# mcu_teensy4_1.net
KiCad netlist of a schematic drawn in EAGLE
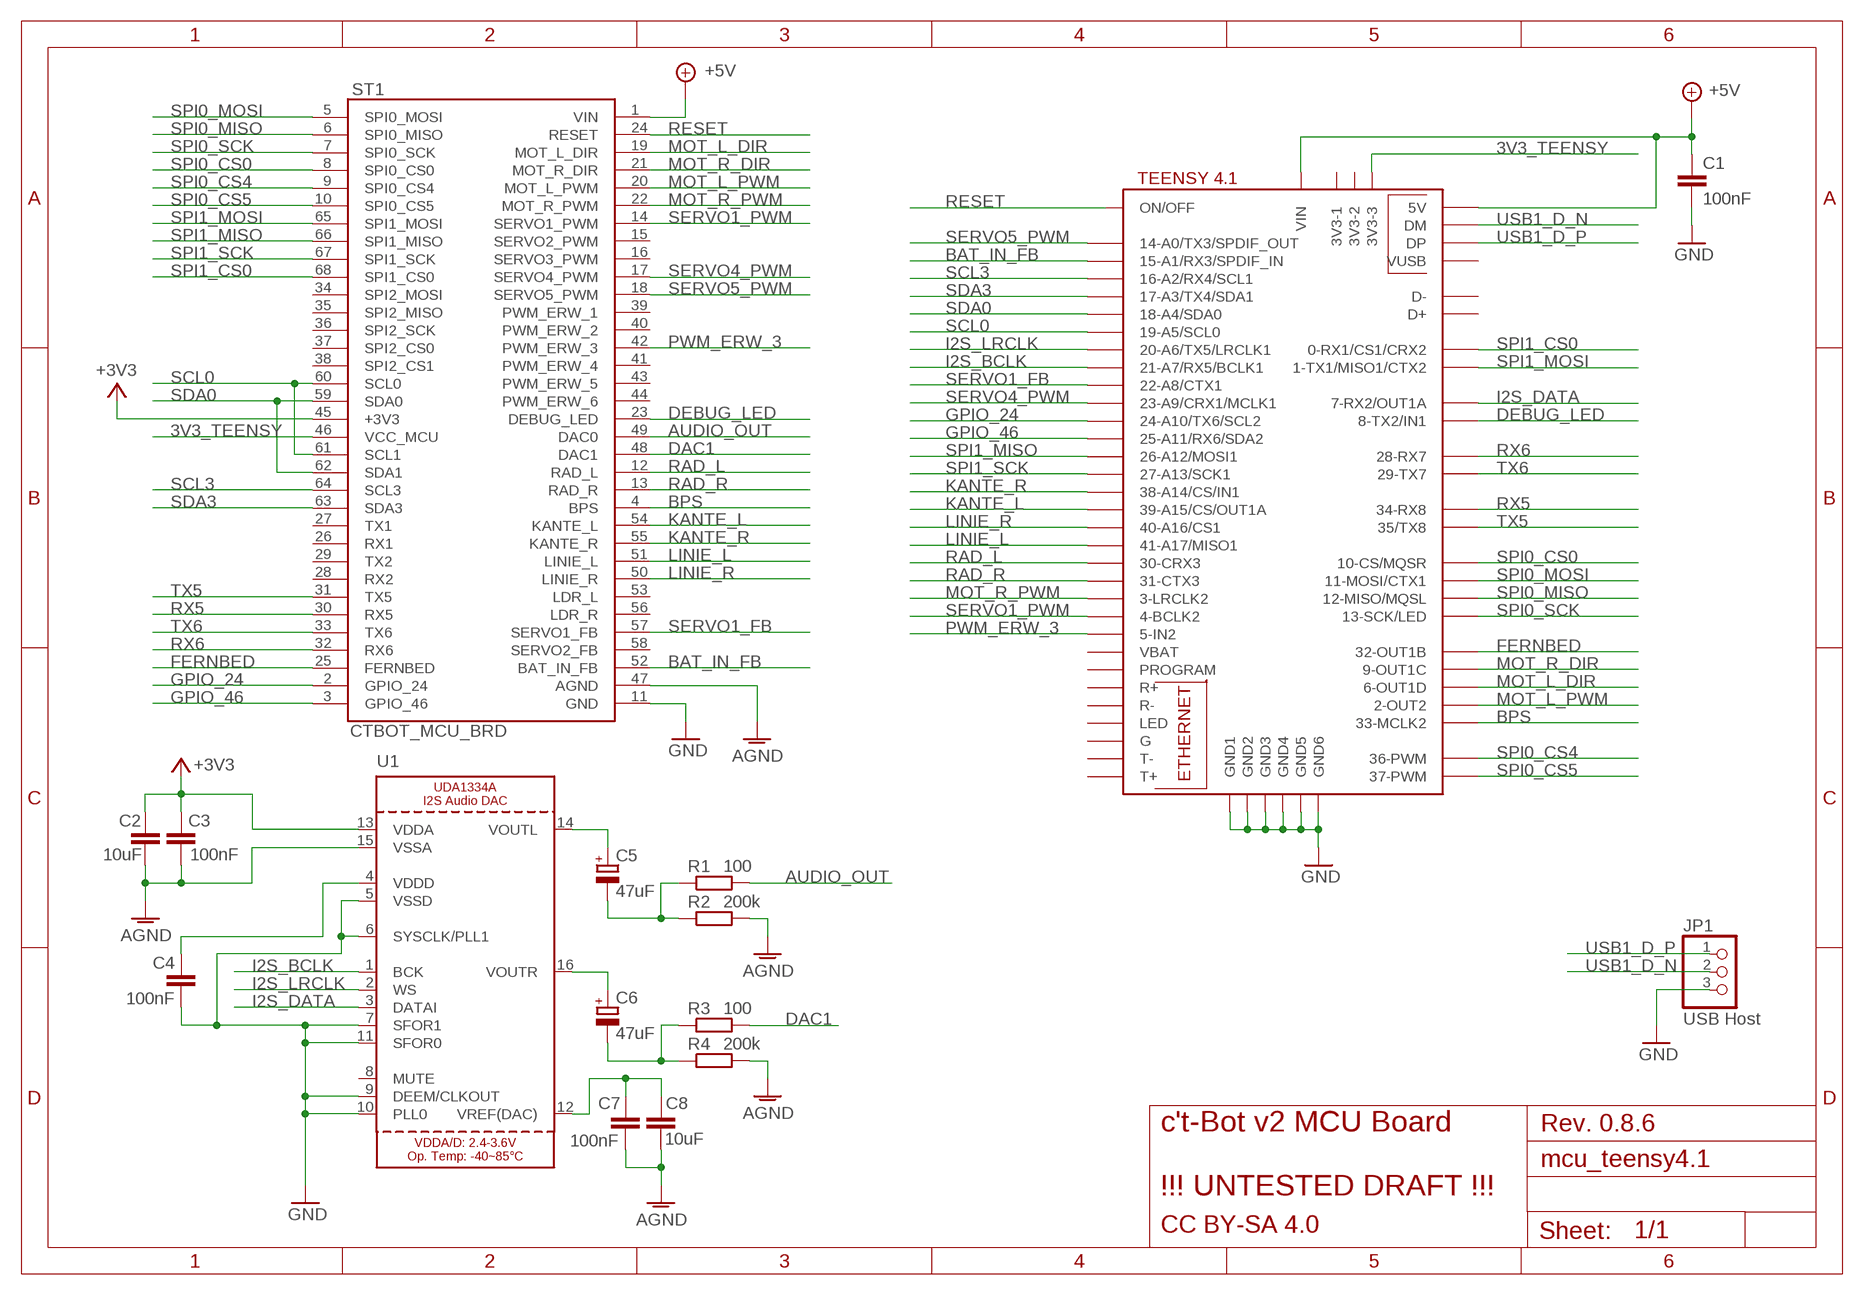
[diagram p0: schematic, sheet 1]

(export (version "E")
  (design (tool "Eeschema 10.0.6"))
  (components
    (comp (ref "C1")
      (value "100nF")
      (footprint "eagle-import:C0805")
      (libsource (lib "eagle-import") (part "C-EUC0805"))
    )
    (comp (ref "C2")
      (value "10uF")
      (footprint "eagle-import:C0805")
      (libsource (lib "eagle-import") (part "C-EUC0805"))
    )
    (comp (ref "C3")
      (value "100nF")
      (footprint "eagle-import:C0805")
      (libsource (lib "eagle-import") (part "C-EUC0805"))
    )
    (comp (ref "C4")
      (value "100nF")
      (footprint "eagle-import:C0805")
      (libsource (lib "eagle-import") (part "C-EUC0805"))
    )
    (comp (ref "C5")
      (value "47uF")
      (footprint "eagle-import:UD-6,3X5,8_NICHICON")
      (libsource (lib "eagle-import") (part "CPOL-EUUD-6,3X8,8"))
    )
    (comp (ref "C6")
      (value "47uF")
      (footprint "eagle-import:UD-6,3X5,8_NICHICON")
      (libsource (lib "eagle-import") (part "CPOL-EUUD-6,3X8,8"))
    )
    (comp (ref "C7")
      (value "100nF")
      (footprint "eagle-import:C0805")
      (libsource (lib "eagle-import") (part "C-EUC0805"))
    )
    (comp (ref "C8")
      (value "10uF")
      (footprint "eagle-import:C0805")
      (libsource (lib "eagle-import") (part "C-EUC0805"))
    )
    (comp (ref "JP1")
      (value "USB Host")
      (footprint "eagle-import:1X03_90")
      (libsource (lib "eagle-import") (part "PINHD-1X3/90"))
    )
    (comp (ref "R1")
      (value "100")
      (footprint "eagle-import:R0805")
      (libsource (lib "eagle-import") (part "R-EU_R0805"))
    )
    (comp (ref "R2")
      (value "200k")
      (footprint "eagle-import:R0805")
      (libsource (lib "eagle-import") (part "R-EU_R0805"))
    )
    (comp (ref "R3")
      (value "100")
      (footprint "eagle-import:R0805")
      (libsource (lib "eagle-import") (part "R-EU_R0805"))
    )
    (comp (ref "R4")
      (value "200k")
      (footprint "eagle-import:R0805")
      (libsource (lib "eagle-import") (part "R-EU_R0805"))
    )
    (comp (ref "ST1")
      (value "CTBOT_MCU_BRD")
      (footprint "eagle-import:DIP66")
      (libsource (lib "eagle-import") (part "CTBOT_MCU_BRD"))
    )
    (comp (ref "U$1")
      (value "TEENSY41")
      (footprint "eagle-import:TEENSY41")
      (libsource (lib "eagle-import") (part "TEENSY41"))
    )
    (comp (ref "U1")
      (value "AUDIO_I2S_UDA1334\"\"")
      (footprint "eagle-import:SSOP16_4.4MM")
      (libsource (lib "eagle-import") (part "AUDIO_I2S_UDA1334{dblquote}{dblquote}"))
    )
  )
  (nets
    (net (code "1") (name "+3V3") (class "Default")
      (node (ref "C2") (pin "1") (pinfunction "1_1") (pintype "passive"))
      (node (ref "C3") (pin "2") (pinfunction "2_2") (pintype "passive"))
      (node (ref "ST1") (pin "45") (pinfunction "+3V3_45") (pintype "power_in"))
      (node (ref "U1") (pin "13") (pinfunction "VDDA_13") (pintype "power_in"))
    )
    (net (code "2") (name "+5V") (class "Default")
      (node (ref "C1") (pin "1") (pinfunction "1_1") (pintype "passive"))
      (node (ref "ST1") (pin "1") (pinfunction "VIN_1") (pintype "power_in"))
      (node (ref "U$1") (pin "+5V") (pinfunction "5V_+5V") (pintype "bidirectional"))
      (node (ref "U$1") (pin "VIN") (pinfunction "VIN_VIN") (pintype "bidirectional"))
    )
    (net (code "3") (name "/3V3_TEENSY") (class "Default")
      (node (ref "ST1") (pin "46") (pinfunction "VCC_MCU_46") (pintype "power_in"))
      (node (ref "U$1") (pin "3V3-3") (pinfunction "3V3-3_3V3-3") (pintype "bidirectional"))
    )
    (net (code "4") (name "/AUDIO_OUT") (class "Default")
      (node (ref "R1") (pin "2") (pinfunction "2_2") (pintype "passive"))
      (node (ref "ST1") (pin "49") (pinfunction "DAC0_49") (pintype "bidirectional"))
    )
    (net (code "5") (name "/BAT_IN_FB") (class "Default")
      (node (ref "ST1") (pin "52") (pinfunction "BAT_IN_FB_52") (pintype "input"))
      (node (ref "U$1") (pin "15-A1/RX3/SPDIF_IN") (pinfunction "15-A1/RX3/SPDIF_IN_15-A1/RX3/SPDIF_IN") (pintype "bidirectional"))
    )
    (net (code "6") (name "/BPS") (class "Default")
      (node (ref "ST1") (pin "4") (pinfunction "BPS_4") (pintype "input"))
      (node (ref "U$1") (pin "33-MCLK2") (pinfunction "33-MCLK2_33-MCLK2") (pintype "bidirectional"))
    )
    (net (code "7") (name "/DAC1") (class "Default")
      (node (ref "R3") (pin "2") (pinfunction "2_2") (pintype "passive"))
      (node (ref "ST1") (pin "48") (pinfunction "DAC1_48") (pintype "bidirectional"))
    )
    (net (code "8") (name "/DEBUG_LED") (class "Default")
      (node (ref "ST1") (pin "23") (pinfunction "DEBUG_LED_23") (pintype "output"))
      (node (ref "U$1") (pin "8-TX2/IN1") (pinfunction "8-TX2/IN1_8-TX2/IN1") (pintype "bidirectional"))
    )
    (net (code "9") (name "/FERNBED") (class "Default")
      (node (ref "ST1") (pin "25") (pinfunction "FERNBED_25") (pintype "bidirectional"))
      (node (ref "U$1") (pin "32-OUT1B") (pinfunction "32-OUT1B_32-OUT1B") (pintype "bidirectional"))
    )
    (net (code "10") (name "/GPIO_24") (class "Default")
      (node (ref "ST1") (pin "2") (pinfunction "GPIO_24_2") (pintype "bidirectional"))
      (node (ref "U$1") (pin "24-A10/TX6/SCL2") (pinfunction "24-A10/TX6/SCL2_24-A10/TX6/SCL2") (pintype "bidirectional"))
    )
    (net (code "11") (name "/GPIO_46") (class "Default")
      (node (ref "ST1") (pin "3") (pinfunction "GPIO_46_3") (pintype "bidirectional"))
      (node (ref "U$1") (pin "25-A11/RX6/SDA2") (pinfunction "25-A11/RX6/SDA2_25-A11/RX6/SDA2") (pintype "bidirectional"))
    )
    (net (code "12") (name "/I2S_BCLK") (class "Default")
      (node (ref "U$1") (pin "21-A7/RX5/BCLK1") (pinfunction "21-A7/RX5/BCLK1_21-A7/RX5/BCLK1") (pintype "bidirectional"))
      (node (ref "U1") (pin "1") (pinfunction "BCK_1") (pintype "input"))
    )
    (net (code "13") (name "/I2S_DATA") (class "Default")
      (node (ref "U$1") (pin "7-RX2/OUT1A") (pinfunction "7-RX2/OUT1A_7-RX2/OUT1A") (pintype "bidirectional"))
      (node (ref "U1") (pin "3") (pinfunction "DATAI_3") (pintype "input"))
    )
    (net (code "14") (name "/I2S_LRCLK") (class "Default")
      (node (ref "U$1") (pin "20-A6/TX5/LRCLK1") (pinfunction "20-A6/TX5/LRCLK1_20-A6/TX5/LRCLK1") (pintype "bidirectional"))
      (node (ref "U1") (pin "2") (pinfunction "WS_2") (pintype "input"))
    )
    (net (code "15") (name "/KANTE_L") (class "Default")
      (node (ref "ST1") (pin "54") (pinfunction "KANTE_L_54") (pintype "input"))
      (node (ref "U$1") (pin "39-A15/CS/OUT1A") (pinfunction "39-A15/CS/OUT1A_39-A15/CS/OUT1A") (pintype "bidirectional"))
    )
    (net (code "16") (name "/KANTE_R") (class "Default")
      (node (ref "ST1") (pin "55") (pinfunction "KANTE_R_55") (pintype "input"))
      (node (ref "U$1") (pin "38-A14/CS/IN1") (pinfunction "38-A14/CS/IN1_38-A14/CS/IN1") (pintype "bidirectional"))
    )
    (net (code "17") (name "/LINIE_L") (class "Default")
      (node (ref "ST1") (pin "51") (pinfunction "LINIE_L_51") (pintype "input"))
      (node (ref "U$1") (pin "41-A17/MISO1") (pinfunction "41-A17/MISO1_41-A17/MISO1") (pintype "bidirectional"))
    )
    (net (code "18") (name "/LINIE_R") (class "Default")
      (node (ref "ST1") (pin "50") (pinfunction "LINIE_R_50") (pintype "input"))
      (node (ref "U$1") (pin "40-A16/CS1") (pinfunction "40-A16/CS1_40-A16/CS1") (pintype "bidirectional"))
    )
    (net (code "19") (name "/MOT_L_DIR") (class "Default")
      (node (ref "ST1") (pin "19") (pinfunction "MOT_L_DIR_19") (pintype "output"))
      (node (ref "U$1") (pin "6-OUT1D") (pinfunction "6-OUT1D_6-OUT1D") (pintype "bidirectional"))
    )
    (net (code "20") (name "/MOT_L_PWM") (class "Default")
      (node (ref "ST1") (pin "20") (pinfunction "MOT_L_PWM_20") (pintype "output"))
      (node (ref "U$1") (pin "2-OUT2") (pinfunction "2-OUT2_2-OUT2") (pintype "bidirectional"))
    )
    (net (code "21") (name "/MOT_R_DIR") (class "Default")
      (node (ref "ST1") (pin "21") (pinfunction "MOT_R_DIR_21") (pintype "output"))
      (node (ref "U$1") (pin "9-OUT1C") (pinfunction "9-OUT1C_9-OUT1C") (pintype "bidirectional"))
    )
    (net (code "22") (name "/MOT_R_PWM") (class "Default")
      (node (ref "ST1") (pin "22") (pinfunction "MOT_R_PWM_22") (pintype "output"))
      (node (ref "U$1") (pin "3-LRCLK2") (pinfunction "3-LRCLK2_3-LRCLK2") (pintype "bidirectional"))
    )
    (net (code "23") (name "/PWM_ERW_3") (class "Default")
      (node (ref "ST1") (pin "42") (pinfunction "PWM_ERW_3_42") (pintype "bidirectional"))
      (node (ref "U$1") (pin "5-IN2") (pinfunction "5-IN2_5-IN2") (pintype "bidirectional"))
    )
    (net (code "24") (name "/RAD_L") (class "Default")
      (node (ref "ST1") (pin "12") (pinfunction "RAD_L_12") (pintype "input"))
      (node (ref "U$1") (pin "30-CRX3") (pinfunction "30-CRX3_30-CRX3") (pintype "bidirectional"))
    )
    (net (code "25") (name "/RAD_R") (class "Default")
      (node (ref "ST1") (pin "13") (pinfunction "RAD_R_13") (pintype "input"))
      (node (ref "U$1") (pin "31-CTX3") (pinfunction "31-CTX3_31-CTX3") (pintype "bidirectional"))
    )
    (net (code "26") (name "/RESET") (class "Default")
      (node (ref "ST1") (pin "24") (pinfunction "RESET_24") (pintype "input"))
      (node (ref "U$1") (pin "ON/OFF") (pinfunction "ON/OFF_ON/OFF") (pintype "bidirectional"))
    )
    (net (code "27") (name "/RX5") (class "Default")
      (node (ref "ST1") (pin "30") (pinfunction "RX5_30") (pintype "input"))
      (node (ref "U$1") (pin "34-RX8") (pinfunction "34-RX8_34-RX8") (pintype "bidirectional"))
    )
    (net (code "28") (name "/RX6") (class "Default")
      (node (ref "ST1") (pin "32") (pinfunction "RX6_32") (pintype "input"))
      (node (ref "U$1") (pin "28-RX7") (pinfunction "28-RX7_28-RX7") (pintype "bidirectional"))
    )
    (net (code "29") (name "/SCL0") (class "Default")
      (node (ref "ST1") (pin "60") (pinfunction "SCL0_60") (pintype "output"))
      (node (ref "ST1") (pin "61") (pinfunction "SCL1_61") (pintype "output"))
      (node (ref "U$1") (pin "19-A5/SCL0") (pinfunction "19-A5/SCL0_19-A5/SCL0") (pintype "bidirectional"))
    )
    (net (code "30") (name "/SCL3") (class "Default")
      (node (ref "ST1") (pin "64") (pinfunction "SCL3_64") (pintype "output"))
      (node (ref "U$1") (pin "16-A2/RX4/SCL1") (pinfunction "16-A2/RX4/SCL1_16-A2/RX4/SCL1") (pintype "bidirectional"))
    )
    (net (code "31") (name "/SDA0") (class "Default")
      (node (ref "ST1") (pin "59") (pinfunction "SDA0_59") (pintype "bidirectional"))
      (node (ref "ST1") (pin "62") (pinfunction "SDA1_62") (pintype "bidirectional"))
      (node (ref "U$1") (pin "18-A4/SDA0") (pinfunction "18-A4/SDA0_18-A4/SDA0") (pintype "bidirectional"))
    )
    (net (code "32") (name "/SDA3") (class "Default")
      (node (ref "ST1") (pin "63") (pinfunction "SDA3_63") (pintype "bidirectional"))
      (node (ref "U$1") (pin "17-A3/TX4/SDA1") (pinfunction "17-A3/TX4/SDA1_17-A3/TX4/SDA1") (pintype "bidirectional"))
    )
    (net (code "33") (name "/SERVO1_FB") (class "Default")
      (node (ref "ST1") (pin "57") (pinfunction "SERVO1_FB_57") (pintype "input"))
      (node (ref "U$1") (pin "22-A8/CTX1") (pinfunction "22-A8/CTX1_22-A8/CTX1") (pintype "bidirectional"))
    )
    (net (code "34") (name "/SERVO1_PWM") (class "Default")
      (node (ref "ST1") (pin "14") (pinfunction "SERVO1_PWM_14") (pintype "output"))
      (node (ref "U$1") (pin "4-BCLK2") (pinfunction "4-BCLK2_4-BCLK2") (pintype "bidirectional"))
    )
    (net (code "35") (name "/SERVO4_PWM") (class "Default")
      (node (ref "ST1") (pin "17") (pinfunction "SERVO4_PWM_17") (pintype "bidirectional"))
      (node (ref "U$1") (pin "23-A9/CRX1/MCLK1") (pinfunction "23-A9/CRX1/MCLK1_23-A9/CRX1/MCLK1") (pintype "bidirectional"))
    )
    (net (code "36") (name "/SERVO5_PWM") (class "Default")
      (node (ref "ST1") (pin "18") (pinfunction "SERVO5_PWM_18") (pintype "bidirectional"))
      (node (ref "U$1") (pin "14-A0/TX3/SPDIF_OUT") (pinfunction "14-A0/TX3/SPDIF_OUT_14-A0/TX3/SPDIF_OUT") (pintype "bidirectional"))
    )
    (net (code "37") (name "/SPI0_CS0") (class "Default")
      (node (ref "ST1") (pin "8") (pinfunction "SPI0_CS0_8") (pintype "bidirectional"))
      (node (ref "U$1") (pin "10-CS\\MQSR") (pinfunction "10-CS/MQSR_10-CS\\MQSR") (pintype "bidirectional"))
    )
    (net (code "38") (name "/SPI0_CS4") (class "Default")
      (node (ref "ST1") (pin "9") (pinfunction "SPI0_CS4_9") (pintype "bidirectional"))
      (node (ref "U$1") (pin "36-PWM") (pinfunction "36-PWM_36-PWM") (pintype "bidirectional"))
    )
    (net (code "39") (name "/SPI0_CS5") (class "Default")
      (node (ref "ST1") (pin "10") (pinfunction "SPI0_CS5_10") (pintype "bidirectional"))
      (node (ref "U$1") (pin "37-PWM") (pinfunction "37-PWM_37-PWM") (pintype "bidirectional"))
    )
    (net (code "40") (name "/SPI0_MISO") (class "Default")
      (node (ref "ST1") (pin "6") (pinfunction "SPI0_MISO_6") (pintype "bidirectional"))
      (node (ref "U$1") (pin "12-MISO/MQSL") (pinfunction "12-MISO/MQSL_12-MISO/MQSL") (pintype "bidirectional"))
    )
    (net (code "41") (name "/SPI0_MOSI") (class "Default")
      (node (ref "ST1") (pin "5") (pinfunction "SPI0_MOSI_5") (pintype "bidirectional"))
      (node (ref "U$1") (pin "11-MOSI/CTX1") (pinfunction "11-MOSI/CTX1_11-MOSI/CTX1") (pintype "bidirectional"))
    )
    (net (code "42") (name "/SPI0_SCK") (class "Default")
      (node (ref "ST1") (pin "7") (pinfunction "SPI0_SCK_7") (pintype "bidirectional"))
      (node (ref "U$1") (pin "13-SCK/LED") (pinfunction "13-SCK/LED_13-SCK/LED") (pintype "bidirectional"))
    )
    (net (code "43") (name "/SPI1_CS0") (class "Default")
      (node (ref "ST1") (pin "68") (pinfunction "SPI1_CS0_68") (pintype "bidirectional"))
      (node (ref "U$1") (pin "0-RX1/CS1/CRX2") (pinfunction "0-RX1/CS1/CRX2_0-RX1/CS1/CRX2") (pintype "bidirectional"))
    )
    (net (code "44") (name "/SPI1_MISO") (class "Default")
      (node (ref "ST1") (pin "66") (pinfunction "SPI1_MISO_66") (pintype "bidirectional"))
      (node (ref "U$1") (pin "26-A12/MOSI1") (pinfunction "26-A12/MOSI1_26-A12/MOSI1") (pintype "bidirectional"))
    )
    (net (code "45") (name "/SPI1_MOSI") (class "Default")
      (node (ref "ST1") (pin "65") (pinfunction "SPI1_MOSI_65") (pintype "bidirectional"))
      (node (ref "U$1") (pin "1-TX1/MISO1/CTX2") (pinfunction "1-TX1/MISO1/CTX2_1-TX1/MISO1/CTX2") (pintype "bidirectional"))
    )
    (net (code "46") (name "/SPI1_SCK") (class "Default")
      (node (ref "ST1") (pin "67") (pinfunction "SPI1_SCK_67") (pintype "bidirectional"))
      (node (ref "U$1") (pin "27-A13/SCK1") (pinfunction "27-A13/SCK1_27-A13/SCK1") (pintype "bidirectional"))
    )
    (net (code "47") (name "/TX5") (class "Default")
      (node (ref "ST1") (pin "31") (pinfunction "TX5_31") (pintype "output"))
      (node (ref "U$1") (pin "35-TX8") (pinfunction "35/TX8_35-TX8") (pintype "bidirectional"))
    )
    (net (code "48") (name "/TX6") (class "Default")
      (node (ref "ST1") (pin "33") (pinfunction "TX6_33") (pintype "output"))
      (node (ref "U$1") (pin "29-TX7") (pinfunction "29-TX7_29-TX7") (pintype "bidirectional"))
    )
    (net (code "49") (name "/USB1_D_N") (class "Default")
      (node (ref "JP1") (pin "2") (pinfunction "2_2") (pintype "passive"))
      (node (ref "U$1") (pin "DM") (pinfunction "DM_DM") (pintype "bidirectional"))
    )
    (net (code "50") (name "/USB1_D_P") (class "Default")
      (node (ref "JP1") (pin "1") (pinfunction "1_1") (pintype "passive"))
      (node (ref "U$1") (pin "DP") (pinfunction "DP_DP") (pintype "bidirectional"))
    )
    (net (code "51") (name "AGND") (class "Default")
      (node (ref "C2") (pin "2") (pinfunction "2_2") (pintype "passive"))
      (node (ref "C3") (pin "1") (pinfunction "1_1") (pintype "passive"))
      (node (ref "C7") (pin "1") (pinfunction "1_1") (pintype "passive"))
      (node (ref "C8") (pin "1") (pinfunction "1_1") (pintype "passive"))
      (node (ref "R2") (pin "2") (pinfunction "2_2") (pintype "passive"))
      (node (ref "R4") (pin "2") (pinfunction "2_2") (pintype "passive"))
      (node (ref "ST1") (pin "47") (pinfunction "AGND_47") (pintype "power_in"))
      (node (ref "U1") (pin "15") (pinfunction "VSSA_15") (pintype "power_in"))
    )
    (net (code "52") (name "GND") (class "Default")
      (node (ref "C1") (pin "2") (pinfunction "2_2") (pintype "passive"))
      (node (ref "C4") (pin "1") (pinfunction "1_1") (pintype "passive"))
      (node (ref "JP1") (pin "3") (pinfunction "3_3") (pintype "passive"))
      (node (ref "ST1") (pin "11") (pinfunction "GND_11") (pintype "power_in"))
      (node (ref "U$1") (pin "GND1") (pinfunction "GND1_GND1") (pintype "bidirectional"))
      (node (ref "U$1") (pin "GND2") (pinfunction "GND2_GND2") (pintype "bidirectional"))
      (node (ref "U$1") (pin "GND3") (pinfunction "GND3_GND3") (pintype "bidirectional"))
      (node (ref "U$1") (pin "GND4") (pinfunction "GND4_GND4") (pintype "bidirectional"))
      (node (ref "U$1") (pin "GND5") (pinfunction "GND5_GND5") (pintype "bidirectional"))
      (node (ref "U$1") (pin "GND6") (pinfunction "GND6_GND6") (pintype "bidirectional"))
      (node (ref "U1") (pin "10") (pinfunction "PLL0_10") (pintype "input"))
      (node (ref "U1") (pin "11") (pinfunction "SFOR0_11") (pintype "input"))
      (node (ref "U1") (pin "5") (pinfunction "VSSD_5") (pintype "power_in"))
      (node (ref "U1") (pin "6") (pinfunction "SYSCLK/PLL1_6") (pintype "input"))
      (node (ref "U1") (pin "7") (pinfunction "SFOR1_7") (pintype "input"))
      (node (ref "U1") (pin "9") (pinfunction "DEEM/CLKOUT_9") (pintype "bidirectional"))
    )
    (net (code "53") (name "Net-(C5-Pad-)") (class "Default")
      (node (ref "C5") (pin "-") (pinfunction "-_-") (pintype "passive"))
      (node (ref "R1") (pin "1") (pinfunction "1_1") (pintype "passive"))
      (node (ref "R2") (pin "1") (pinfunction "1_1") (pintype "passive"))
    )
    (net (code "54") (name "Net-(C6-Pad-)") (class "Default")
      (node (ref "C6") (pin "-") (pinfunction "-_-") (pintype "passive"))
      (node (ref "R3") (pin "1") (pinfunction "1_1") (pintype "passive"))
      (node (ref "R4") (pin "1") (pinfunction "1_1") (pintype "passive"))
    )
    (net (code "55") (name "Net-(U1-VDDD)") (class "Default")
      (node (ref "C4") (pin "2") (pinfunction "2_2") (pintype "passive"))
      (node (ref "U1") (pin "4") (pinfunction "VDDD_4") (pintype "power_in"))
    )
    (net (code "56") (name "Net-(U1-VOUTL)") (class "Default")
      (node (ref "C5") (pin "+") (pinfunction "+_+") (pintype "passive"))
      (node (ref "U1") (pin "14") (pinfunction "VOUTL_14") (pintype "output"))
    )
    (net (code "57") (name "Net-(U1-VOUTR)") (class "Default")
      (node (ref "C6") (pin "+") (pinfunction "+_+") (pintype "passive"))
      (node (ref "U1") (pin "16") (pinfunction "VOUTR_16") (pintype "output"))
    )
    (net (code "58") (name "Net-(U1-VREF(DAC))") (class "Default")
      (node (ref "C7") (pin "2") (pinfunction "2_2") (pintype "passive"))
      (node (ref "C8") (pin "2") (pinfunction "2_2") (pintype "passive"))
      (node (ref "U1") (pin "12") (pinfunction "VREF(DAC)_12") (pintype "output"))
    )
    (net (code "59") (name "unconnected-(ST1-LDR_L-Pad53)") (class "Default")
      (node (ref "ST1") (pin "53") (pinfunction "LDR_L_53") (pintype "input"))
    )
    (net (code "60") (name "unconnected-(ST1-LDR_R-Pad56)") (class "Default")
      (node (ref "ST1") (pin "56") (pinfunction "LDR_R_56") (pintype "input"))
    )
    (net (code "61") (name "unconnected-(ST1-PWM_ERW_1-Pad39)") (class "Default")
      (node (ref "ST1") (pin "39") (pinfunction "PWM_ERW_1_39") (pintype "bidirectional"))
    )
    (net (code "62") (name "unconnected-(ST1-PWM_ERW_2-Pad40)") (class "Default")
      (node (ref "ST1") (pin "40") (pinfunction "PWM_ERW_2_40") (pintype "bidirectional"))
    )
    (net (code "63") (name "unconnected-(ST1-PWM_ERW_4-Pad41)") (class "Default")
      (node (ref "ST1") (pin "41") (pinfunction "PWM_ERW_4_41") (pintype "bidirectional"))
    )
    (net (code "64") (name "unconnected-(ST1-PWM_ERW_5-Pad43)") (class "Default")
      (node (ref "ST1") (pin "43") (pinfunction "PWM_ERW_5_43") (pintype "bidirectional"))
    )
    (net (code "65") (name "unconnected-(ST1-PWM_ERW_6-Pad44)") (class "Default")
      (node (ref "ST1") (pin "44") (pinfunction "PWM_ERW_6_44") (pintype "bidirectional"))
    )
    (net (code "66") (name "unconnected-(ST1-RX1-Pad26)") (class "Default")
      (node (ref "ST1") (pin "26") (pinfunction "RX1_26") (pintype "input"))
    )
    (net (code "67") (name "unconnected-(ST1-RX2-Pad28)") (class "Default")
      (node (ref "ST1") (pin "28") (pinfunction "RX2_28") (pintype "input"))
    )
    (net (code "68") (name "unconnected-(ST1-SERVO2_FB-Pad58)") (class "Default")
      (node (ref "ST1") (pin "58") (pinfunction "SERVO2_FB_58") (pintype "input"))
    )
    (net (code "69") (name "unconnected-(ST1-SERVO2_PWM-Pad15)") (class "Default")
      (node (ref "ST1") (pin "15") (pinfunction "SERVO2_PWM_15") (pintype "output"))
    )
    (net (code "70") (name "unconnected-(ST1-SERVO3_PWM-Pad16)") (class "Default")
      (node (ref "ST1") (pin "16") (pinfunction "SERVO3_PWM_16") (pintype "bidirectional"))
    )
    (net (code "71") (name "unconnected-(ST1-SPI2_CS0-Pad37)") (class "Default")
      (node (ref "ST1") (pin "37") (pinfunction "SPI2_CS0_37") (pintype "bidirectional"))
    )
    (net (code "72") (name "unconnected-(ST1-SPI2_CS1-Pad38)") (class "Default")
      (node (ref "ST1") (pin "38") (pinfunction "SPI2_CS1_38") (pintype "bidirectional"))
    )
    (net (code "73") (name "unconnected-(ST1-SPI2_MISO-Pad35)") (class "Default")
      (node (ref "ST1") (pin "35") (pinfunction "SPI2_MISO_35") (pintype "bidirectional"))
    )
    (net (code "74") (name "unconnected-(ST1-SPI2_MOSI-Pad34)") (class "Default")
      (node (ref "ST1") (pin "34") (pinfunction "SPI2_MOSI_34") (pintype "bidirectional"))
    )
    (net (code "75") (name "unconnected-(ST1-SPI2_SCK-Pad36)") (class "Default")
      (node (ref "ST1") (pin "36") (pinfunction "SPI2_SCK_36") (pintype "bidirectional"))
    )
    (net (code "76") (name "unconnected-(ST1-TX1-Pad27)") (class "Default")
      (node (ref "ST1") (pin "27") (pinfunction "TX1_27") (pintype "output"))
    )
    (net (code "77") (name "unconnected-(ST1-TX2-Pad29)") (class "Default")
      (node (ref "ST1") (pin "29") (pinfunction "TX2_29") (pintype "input"))
    )
    (net (code "78") (name "unconnected-(U$1-Pad3V3-1)") (class "Default")
      (node (ref "U$1") (pin "3V3-1") (pinfunction "3V3-1_3V3-1") (pintype "bidirectional"))
    )
    (net (code "79") (name "unconnected-(U$1-Pad3V3-2)") (class "Default")
      (node (ref "U$1") (pin "3V3-2") (pinfunction "3V3-2_3V3-2") (pintype "bidirectional"))
    )
    (net (code "80") (name "unconnected-(U$1-PadD+)") (class "Default")
      (node (ref "U$1") (pin "D+") (pinfunction "D+_D+") (pintype "bidirectional"))
    )
    (net (code "81") (name "unconnected-(U$1-PadD-)") (class "Default")
      (node (ref "U$1") (pin "D-") (pinfunction "D-_D-") (pintype "bidirectional"))
    )
    (net (code "82") (name "unconnected-(U$1-PadG)") (class "Default")
      (node (ref "U$1") (pin "G") (pinfunction "G_G") (pintype "bidirectional"))
    )
    (net (code "83") (name "unconnected-(U$1-PadLED)") (class "Default")
      (node (ref "U$1") (pin "LED") (pinfunction "LED_LED") (pintype "bidirectional"))
    )
    (net (code "84") (name "unconnected-(U$1-PadPROGRAM)") (class "Default")
      (node (ref "U$1") (pin "PROGRAM") (pinfunction "PROGRAM_PROGRAM") (pintype "bidirectional"))
    )
    (net (code "85") (name "unconnected-(U$1-PadR+)") (class "Default")
      (node (ref "U$1") (pin "R+") (pinfunction "R+_R+") (pintype "bidirectional"))
    )
    (net (code "86") (name "unconnected-(U$1-PadR-)") (class "Default")
      (node (ref "U$1") (pin "R-") (pinfunction "R-_R-") (pintype "bidirectional"))
    )
    (net (code "87") (name "unconnected-(U$1-PadT+)") (class "Default")
      (node (ref "U$1") (pin "T+") (pinfunction "T+_T+") (pintype "bidirectional"))
    )
    (net (code "88") (name "unconnected-(U$1-PadT-)") (class "Default")
      (node (ref "U$1") (pin "T-") (pinfunction "T-_T-") (pintype "bidirectional"))
    )
    (net (code "89") (name "unconnected-(U$1-PadVBAT)") (class "Default")
      (node (ref "U$1") (pin "VBAT") (pinfunction "VBAT_VBAT") (pintype "bidirectional"))
    )
    (net (code "90") (name "unconnected-(U$1-PadVUSB)") (class "Default")
      (node (ref "U$1") (pin "VUSB") (pinfunction "VUSB_VUSB") (pintype "bidirectional"))
    )
    (net (code "91") (name "unconnected-(U1-MUTE-Pad8)") (class "Default")
      (node (ref "U1") (pin "8") (pinfunction "MUTE_8") (pintype "input"))
    )
  )
)
